# valiant_v1.net
KiCad netlist of a schematic drawn in EAGLE
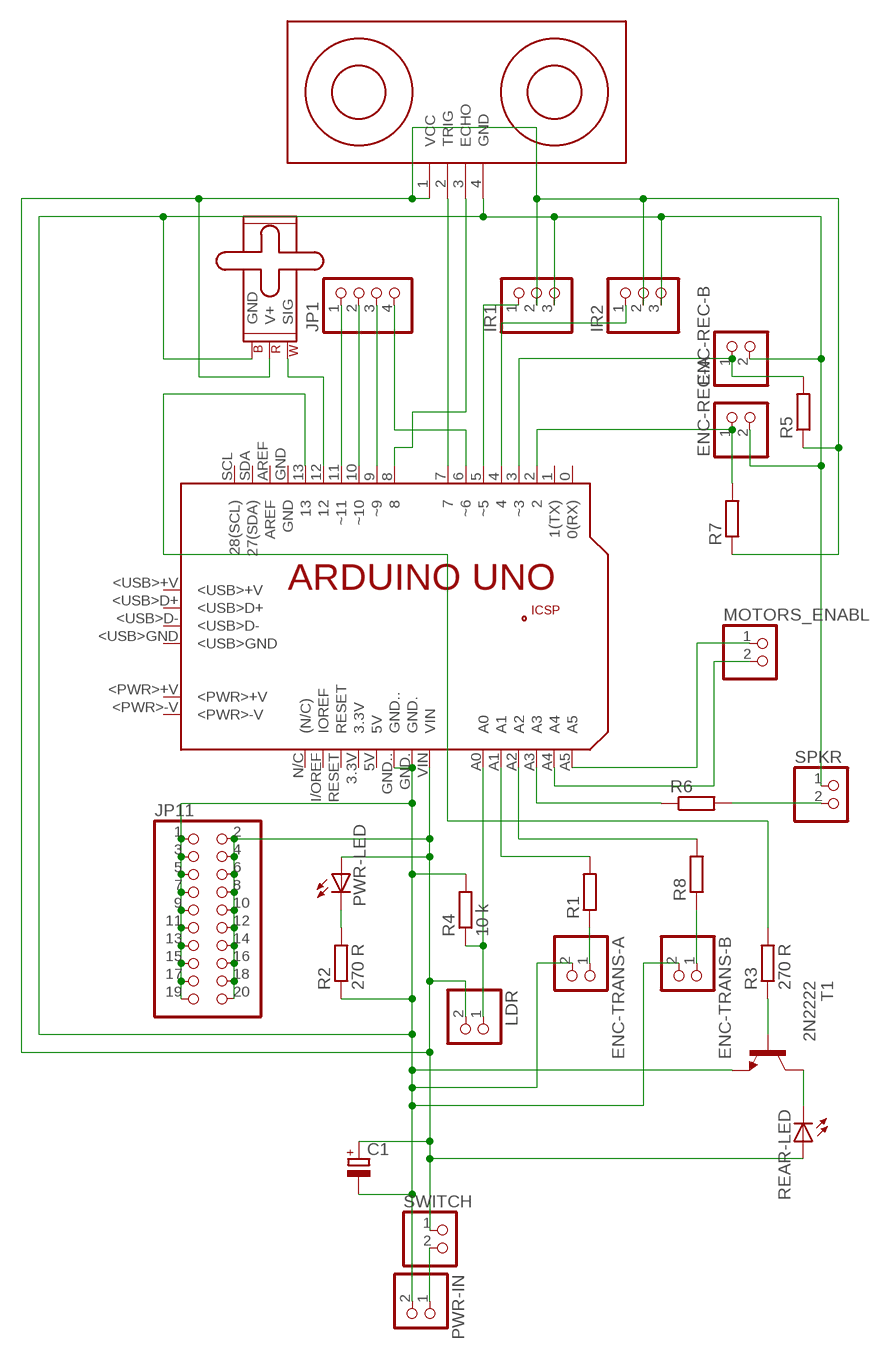
[diagram p0: schematic, sheet 1]

(export (version "E")
  (design (tool "Eeschema 10.0.6"))
  (components
    (comp (ref "C1")
      (value "CPOL-EUE2,5-6E")
      (footprint "eagle-import:E2,5-6E")
      (libsource (lib "eagle-import") (part "CPOL-EUE2,5-6E"))
    )
    (comp (ref "ENC-REC-A")
      (value "PINHD-1X2")
      (footprint "eagle-import:1X02")
      (libsource (lib "eagle-import") (part "PINHD-1X2"))
    )
    (comp (ref "ENC-REC-B")
      (value "PINHD-1X2")
      (footprint "eagle-import:1X02")
      (libsource (lib "eagle-import") (part "PINHD-1X2"))
    )
    (comp (ref "ENC-TRANS-A")
      (value "PINHD-1X2")
      (footprint "eagle-import:1X02")
      (libsource (lib "eagle-import") (part "PINHD-1X2"))
    )
    (comp (ref "ENC-TRANS-B")
      (value "PINHD-1X2")
      (footprint "eagle-import:1X02")
      (libsource (lib "eagle-import") (part "PINHD-1X2"))
    )
    (comp (ref "IR1")
      (value "PINHD-1X3")
      (footprint "eagle-import:1X03")
      (libsource (lib "eagle-import") (part "PINHD-1X3"))
    )
    (comp (ref "IR2")
      (value "PINHD-1X3")
      (footprint "eagle-import:1X03")
      (libsource (lib "eagle-import") (part "PINHD-1X3"))
    )
    (comp (ref "JP1")
      (value "PINHD-1X4")
      (footprint "eagle-import:1X04")
      (libsource (lib "eagle-import") (part "PINHD-1X4"))
    )
    (comp (ref "JP11")
      (value "PINHD-2X10")
      (footprint "eagle-import:2X10")
      (libsource (lib "eagle-import") (part "PINHD-2X10"))
    )
    (comp (ref "LDR")
      (value "PINHD-1X2")
      (footprint "eagle-import:1X02")
      (libsource (lib "eagle-import") (part "PINHD-1X2"))
    )
    (comp (ref "M1")
      (value "SMALL_SERVO")
      (footprint "eagle-import:1X03")
      (libsource (lib "eagle-import") (part "SMALL_SERVO"))
    )
    (comp (ref "MOTORS_ENABLE")
      (value "PINHD-1X2")
      (footprint "eagle-import:1X02")
      (libsource (lib "eagle-import") (part "PINHD-1X2"))
    )
    (comp (ref "PCB1")
      (value "ARDUINO_UNO")
      (footprint "eagle-import:ARDUINO_UNO")
      (libsource (lib "eagle-import") (part "ARDUINO_UNO"))
    )
    (comp (ref "PWR-IN")
      (value "PINHD-1X2")
      (footprint "eagle-import:1X02")
      (libsource (lib "eagle-import") (part "PINHD-1X2"))
    )
    (comp (ref "PWR-LED")
      (value "LED5MM")
      (footprint "eagle-import:LED5MM")
      (libsource (lib "eagle-import") (part "LED5MM"))
    )
    (comp (ref "R1")
      (value "R-EU_0204/7")
      (footprint "eagle-import:0204_7")
      (libsource (lib "eagle-import") (part "R-EU_0204/7"))
    )
    (comp (ref "R2")
      (value "270 R")
      (footprint "eagle-import:0204_7")
      (libsource (lib "eagle-import") (part "R-EU_0204/7"))
    )
    (comp (ref "R3")
      (value "270 R")
      (footprint "eagle-import:0204_7")
      (libsource (lib "eagle-import") (part "R-EU_0204/7"))
    )
    (comp (ref "R4")
      (value "10 k")
      (footprint "eagle-import:0204_7")
      (libsource (lib "eagle-import") (part "R-EU_0204/7"))
    )
    (comp (ref "R5")
      (value "R-EU_0204/7")
      (footprint "eagle-import:0204_7")
      (libsource (lib "eagle-import") (part "R-EU_0204/7"))
    )
    (comp (ref "R6")
      (value "R-EU_0204/7")
      (footprint "eagle-import:0204_7")
      (libsource (lib "eagle-import") (part "R-EU_0204/7"))
    )
    (comp (ref "R7")
      (value "R-EU_0204/7")
      (footprint "eagle-import:0204_7")
      (libsource (lib "eagle-import") (part "R-EU_0204/7"))
    )
    (comp (ref "R8")
      (value "R-EU_0204/7")
      (footprint "eagle-import:0204_7")
      (libsource (lib "eagle-import") (part "R-EU_0204/7"))
    )
    (comp (ref "REAR-LED")
      (value "LED5MM")
      (footprint "eagle-import:LED5MM")
      (libsource (lib "eagle-import") (part "LED5MM"))
    )
    (comp (ref "SPKR")
      (value "PINHD-1X2")
      (footprint "eagle-import:1X02")
      (libsource (lib "eagle-import") (part "PINHD-1X2"))
    )
    (comp (ref "SWITCH")
      (value "PINHD-1X2")
      (footprint "eagle-import:1X02")
      (libsource (lib "eagle-import") (part "PINHD-1X2"))
    )
    (comp (ref "T1")
      (value "2N2222")
      (footprint "eagle-import:TO92-EBC-OVAL")
      (libsource (lib "eagle-import") (part "2N2222"))
    )
    (comp (ref "U$1")
      (value "ULTRASONIC-HC-SR04#V")
      (footprint "eagle-import:ULTRASONIC-HC-SR04#V")
      (libsource (lib "eagle-import") (part "ULTRASONIC-HC-SR04#V"))
    )
  )
  (nets
    (net (code "1") (name "Net-(ENC-REC-A-Pad1)") (class "Default")
      (node (ref "ENC-REC-A") (pin "1") (pinfunction "1_1") (pintype "passive"))
      (node (ref "PCB1") (pin "2") (pinfunction "2_2") (pintype "bidirectional"))
      (node (ref "R7") (pin "2") (pinfunction "2_2") (pintype "passive"))
    )
    (net (code "2") (name "Net-(ENC-TRANS-A-Pad1)") (class "Default")
      (node (ref "ENC-TRANS-A") (pin "1") (pinfunction "1_1") (pintype "passive"))
      (node (ref "R1") (pin "1") (pinfunction "1_1") (pintype "passive"))
    )
    (net (code "3") (name "Net-(ENC-TRANS-B-Pad1)") (class "Default")
      (node (ref "ENC-TRANS-B") (pin "1") (pinfunction "1_1") (pintype "passive"))
      (node (ref "R8") (pin "1") (pinfunction "1_1") (pintype "passive"))
    )
    (net (code "4") (name "Net-(IR2-Pad1)") (class "Default")
      (node (ref "IR2") (pin "1") (pinfunction "1_1") (pintype "passive"))
      (node (ref "PCB1") (pin "4") (pinfunction "4_4") (pintype "bidirectional"))
    )
    (net (code "5") (name "Net-(LDR-Pad1)") (class "Default")
      (node (ref "LDR") (pin "1") (pinfunction "1_1") (pintype "passive"))
      (node (ref "PCB1") (pin "A0") (pinfunction "A0_A0") (pintype "bidirectional"))
      (node (ref "R4") (pin "1") (pinfunction "1_1") (pintype "passive"))
    )
    (net (code "6") (name "Net-(M1-GND)") (class "Default")
      (node (ref "C1") (pin "-") (pinfunction "-_-") (pintype "passive"))
      (node (ref "ENC-REC-A") (pin "2") (pinfunction "2_2") (pintype "passive"))
      (node (ref "ENC-REC-B") (pin "2") (pinfunction "2_2") (pintype "passive"))
      (node (ref "ENC-TRANS-A") (pin "2") (pinfunction "2_2") (pintype "passive"))
      (node (ref "ENC-TRANS-B") (pin "2") (pinfunction "2_2") (pintype "passive"))
      (node (ref "IR1") (pin "3") (pinfunction "3_3") (pintype "passive"))
      (node (ref "IR2") (pin "3") (pinfunction "3_3") (pintype "passive"))
      (node (ref "JP11") (pin "1") (pinfunction "1_1") (pintype "passive"))
      (node (ref "JP11") (pin "11") (pinfunction "11_11") (pintype "passive"))
      (node (ref "JP11") (pin "13") (pinfunction "13_13") (pintype "passive"))
      (node (ref "JP11") (pin "15") (pinfunction "15_15") (pintype "passive"))
      (node (ref "JP11") (pin "17") (pinfunction "17_17") (pintype "passive"))
      (node (ref "JP11") (pin "19") (pinfunction "19_19") (pintype "passive"))
      (node (ref "JP11") (pin "3") (pinfunction "3_3") (pintype "passive"))
      (node (ref "JP11") (pin "5") (pinfunction "5_5") (pintype "passive"))
      (node (ref "JP11") (pin "7") (pinfunction "7_7") (pintype "passive"))
      (node (ref "JP11") (pin "9") (pinfunction "9_9") (pintype "passive"))
      (node (ref "M1") (pin "3") (pinfunction "GND_3") (pintype "bidirectional"))
      (node (ref "PCB1") (pin "GND.") (pinfunction "GND._GND.") (pintype "bidirectional"))
      (node (ref "PCB1") (pin "GND..") (pinfunction "GND.._GND..") (pintype "bidirectional"))
      (node (ref "PWR-IN") (pin "2") (pinfunction "2_2") (pintype "passive"))
      (node (ref "R2") (pin "1") (pinfunction "1_1") (pintype "passive"))
      (node (ref "R4") (pin "2") (pinfunction "2_2") (pintype "passive"))
      (node (ref "SPKR") (pin "1") (pinfunction "1_1") (pintype "passive"))
      (node (ref "T1") (pin "E") (pinfunction "E_E") (pintype "passive"))
      (node (ref "U$1") (pin "4") (pinfunction "GND_4") (pintype "power_in"))
    )
    (net (code "7") (name "Net-(M1-SIG)") (class "Default")
      (node (ref "M1") (pin "1") (pinfunction "SIG_1") (pintype "bidirectional"))
      (node (ref "PCB1") (pin "12") (pinfunction "12_12") (pintype "bidirectional"))
    )
    (net (code "8") (name "Net-(M1-V+)") (class "Default")
      (node (ref "C1") (pin "+") (pinfunction "+_+") (pintype "passive"))
      (node (ref "IR1") (pin "2") (pinfunction "2_2") (pintype "passive"))
      (node (ref "IR2") (pin "2") (pinfunction "2_2") (pintype "passive"))
      (node (ref "JP11") (pin "10") (pinfunction "10_10") (pintype "passive"))
      (node (ref "JP11") (pin "12") (pinfunction "12_12") (pintype "passive"))
      (node (ref "JP11") (pin "14") (pinfunction "14_14") (pintype "passive"))
      (node (ref "JP11") (pin "16") (pinfunction "16_16") (pintype "passive"))
      (node (ref "JP11") (pin "18") (pinfunction "18_18") (pintype "passive"))
      (node (ref "JP11") (pin "2") (pinfunction "2_2") (pintype "passive"))
      (node (ref "JP11") (pin "20") (pinfunction "20_20") (pintype "passive"))
      (node (ref "JP11") (pin "4") (pinfunction "4_4") (pintype "passive"))
      (node (ref "JP11") (pin "6") (pinfunction "6_6") (pintype "passive"))
      (node (ref "JP11") (pin "8") (pinfunction "8_8") (pintype "passive"))
      (node (ref "LDR") (pin "2") (pinfunction "2_2") (pintype "passive"))
      (node (ref "M1") (pin "2") (pinfunction "V+_2") (pintype "bidirectional"))
      (node (ref "PCB1") (pin "VIN") (pinfunction "VIN_VIN") (pintype "bidirectional"))
      (node (ref "PWR-LED") (pin "A") (pinfunction "A_A") (pintype "passive"))
      (node (ref "R5") (pin "1") (pinfunction "1_1") (pintype "passive"))
      (node (ref "R7") (pin "1") (pinfunction "1_1") (pintype "passive"))
      (node (ref "REAR-LED") (pin "A") (pinfunction "A_A") (pintype "passive"))
      (node (ref "SWITCH") (pin "1") (pinfunction "1_1") (pintype "passive"))
      (node (ref "U$1") (pin "1") (pinfunction "VCC_1") (pintype "power_in"))
    )
    (net (code "9") (name "Net-(MOTORS_ENABLE-Pad1)") (class "Default")
      (node (ref "MOTORS_ENABLE") (pin "1") (pinfunction "1_1") (pintype "passive"))
      (node (ref "PCB1") (pin "A5") (pinfunction "A5_A5") (pintype "bidirectional"))
    )
    (net (code "10") (name "Net-(MOTORS_ENABLE-Pad2)") (class "Default")
      (node (ref "MOTORS_ENABLE") (pin "2") (pinfunction "2_2") (pintype "passive"))
      (node (ref "PCB1") (pin "A4") (pinfunction "A4_A4") (pintype "bidirectional"))
    )
    (net (code "11") (name "Net-(PCB1-Pad13)") (class "Default")
      (node (ref "PCB1") (pin "13") (pinfunction "13_13") (pintype "bidirectional"))
      (node (ref "R3") (pin "2") (pinfunction "2_2") (pintype "passive"))
    )
    (net (code "12") (name "Net-(PCB1-PadA1)") (class "Default")
      (node (ref "PCB1") (pin "A1") (pinfunction "A1_A1") (pintype "bidirectional"))
      (node (ref "R1") (pin "2") (pinfunction "2_2") (pintype "passive"))
    )
    (net (code "13") (name "Net-(PCB1-PadA2)") (class "Default")
      (node (ref "PCB1") (pin "A2") (pinfunction "A2_A2") (pintype "bidirectional"))
      (node (ref "R8") (pin "2") (pinfunction "2_2") (pintype "passive"))
    )
    (net (code "14") (name "Net-(PCB1-PadA3)") (class "Default")
      (node (ref "PCB1") (pin "A3") (pinfunction "A3_A3") (pintype "bidirectional"))
      (node (ref "R6") (pin "1") (pinfunction "1_1") (pintype "passive"))
    )
    (net (code "15") (name "Net-(PCB1-~{3})") (class "Default")
      (node (ref "ENC-REC-B") (pin "1") (pinfunction "1_1") (pintype "passive"))
      (node (ref "PCB1") (pin "3") (pinfunction "~{3}_3") (pintype "bidirectional"))
      (node (ref "R5") (pin "2") (pinfunction "2_2") (pintype "passive"))
    )
    (net (code "16") (name "Net-(PCB1-~{5})") (class "Default")
      (node (ref "IR1") (pin "1") (pinfunction "1_1") (pintype "passive"))
      (node (ref "PCB1") (pin "5") (pinfunction "~{5}_5") (pintype "bidirectional"))
    )
    (net (code "17") (name "Net-(PCB1-~{6})") (class "Default")
      (node (ref "JP1") (pin "4") (pinfunction "4_4") (pintype "passive"))
      (node (ref "PCB1") (pin "6") (pinfunction "~{6}_6") (pintype "bidirectional"))
    )
    (net (code "18") (name "Net-(PCB1-~{9})") (class "Default")
      (node (ref "JP1") (pin "3") (pinfunction "3_3") (pintype "passive"))
      (node (ref "PCB1") (pin "9") (pinfunction "~{9}_9") (pintype "bidirectional"))
    )
    (net (code "19") (name "Net-(PCB1-~{10})") (class "Default")
      (node (ref "JP1") (pin "2") (pinfunction "2_2") (pintype "passive"))
      (node (ref "PCB1") (pin "10") (pinfunction "~{10}_10") (pintype "bidirectional"))
    )
    (net (code "20") (name "Net-(PCB1-~{11})") (class "Default")
      (node (ref "JP1") (pin "1") (pinfunction "1_1") (pintype "passive"))
      (node (ref "PCB1") (pin "11") (pinfunction "~{11}_11") (pintype "bidirectional"))
    )
    (net (code "21") (name "Net-(PWR-IN-Pad1)") (class "Default")
      (node (ref "PWR-IN") (pin "1") (pinfunction "1_1") (pintype "passive"))
      (node (ref "SWITCH") (pin "2") (pinfunction "2_2") (pintype "passive"))
    )
    (net (code "22") (name "Net-(PWR-LED-C)") (class "Default")
      (node (ref "PWR-LED") (pin "K") (pinfunction "C_K") (pintype "passive"))
      (node (ref "R2") (pin "2") (pinfunction "2_2") (pintype "passive"))
    )
    (net (code "23") (name "Net-(R3-Pad1)") (class "Default")
      (node (ref "R3") (pin "1") (pinfunction "1_1") (pintype "passive"))
      (node (ref "T1") (pin "B") (pinfunction "B_B") (pintype "passive"))
    )
    (net (code "24") (name "Net-(R6-Pad2)") (class "Default")
      (node (ref "R6") (pin "2") (pinfunction "2_2") (pintype "passive"))
      (node (ref "SPKR") (pin "2") (pinfunction "2_2") (pintype "passive"))
    )
    (net (code "25") (name "Net-(REAR-LED-C)") (class "Default")
      (node (ref "REAR-LED") (pin "K") (pinfunction "C_K") (pintype "passive"))
      (node (ref "T1") (pin "C") (pinfunction "C_C") (pintype "passive"))
    )
    (net (code "26") (name "Net-(U$1-ECHO)") (class "Default")
      (node (ref "PCB1") (pin "8") (pinfunction "8_8") (pintype "bidirectional"))
      (node (ref "U$1") (pin "3") (pinfunction "ECHO_3") (pintype "output"))
    )
    (net (code "27") (name "Net-(U$1-TRIG)") (class "Default")
      (node (ref "PCB1") (pin "7") (pinfunction "7_7") (pintype "bidirectional"))
      (node (ref "U$1") (pin "2") (pinfunction "TRIG_2") (pintype "input"))
    )
    (net (code "28") (name "unconnected-(PCB1-(N{slash}C)-PadN{slash}C)") (class "Default")
      (node (ref "PCB1") (pin "N/C") (pinfunction "(N/C)_N/C") (pintype "bidirectional"))
    )
    (net (code "29") (name "unconnected-(PCB1-0(RX)-Pad0)") (class "Default")
      (node (ref "PCB1") (pin "0") (pinfunction "0(RX)_0") (pintype "bidirectional"))
    )
    (net (code "30") (name "unconnected-(PCB1-1(TX)-Pad1)") (class "Default")
      (node (ref "PCB1") (pin "1") (pinfunction "1(TX)_1") (pintype "bidirectional"))
    )
    (net (code "31") (name "unconnected-(PCB1-27(SDA)-PadSDA)") (class "Default")
      (node (ref "PCB1") (pin "SDA") (pinfunction "27(SDA)_SDA") (pintype "bidirectional"))
    )
    (net (code "32") (name "unconnected-(PCB1-28(SCL)-PadSCL)") (class "Default")
      (node (ref "PCB1") (pin "SCL") (pinfunction "28(SCL)_SCL") (pintype "bidirectional"))
    )
    (net (code "33") (name "unconnected-(PCB1-IOREF-PadI{slash}OREF)") (class "Default")
      (node (ref "PCB1") (pin "I/OREF") (pinfunction "IOREF_I/OREF") (pintype "bidirectional"))
    )
    (net (code "34") (name "unconnected-(PCB1-Pad+5V)") (class "Default")
      (node (ref "PCB1") (pin "+5V") (pinfunction "+5V_+5V") (pintype "bidirectional"))
    )
    (net (code "35") (name "unconnected-(PCB1-Pad3.3V)") (class "Default")
      (node (ref "PCB1") (pin "3.3V") (pinfunction "3.3V_3.3V") (pintype "bidirectional"))
    )
    (net (code "36") (name "unconnected-(PCB1-Pad5V)") (class "Default")
      (node (ref "PCB1") (pin "5V") (pinfunction "5V_5V") (pintype "bidirectional"))
    )
    (net (code "37") (name "unconnected-(PCB1-Pad<PWR>+V)") (class "Default")
      (node (ref "PCB1") (pin "<PWR>+V") (pinfunction "<PWR>+V_<PWR>+V") (pintype "bidirectional"))
    )
    (net (code "38") (name "unconnected-(PCB1-Pad<PWR>-V)") (class "Default")
      (node (ref "PCB1") (pin "<PWR>-V") (pinfunction "<PWR>-V_<PWR>-V") (pintype "bidirectional"))
    )
    (net (code "39") (name "unconnected-(PCB1-Pad<USB>+V)") (class "Default")
      (node (ref "PCB1") (pin "<USB>+V") (pinfunction "<USB>+V_<USB>+V") (pintype "bidirectional"))
    )
    (net (code "40") (name "unconnected-(PCB1-Pad<USB>D+)") (class "Default")
      (node (ref "PCB1") (pin "<USB>D+") (pinfunction "<USB>D+_<USB>D+") (pintype "bidirectional"))
    )
    (net (code "41") (name "unconnected-(PCB1-Pad<USB>D-)") (class "Default")
      (node (ref "PCB1") (pin "<USB>D-") (pinfunction "<USB>D-_<USB>D-") (pintype "bidirectional"))
    )
    (net (code "42") (name "unconnected-(PCB1-Pad<USB>GND)") (class "Default")
      (node (ref "PCB1") (pin "<USB>GND") (pinfunction "<USB>GND_<USB>GND") (pintype "bidirectional"))
    )
    (net (code "43") (name "unconnected-(PCB1-PadAREF)") (class "Default")
      (node (ref "PCB1") (pin "AREF") (pinfunction "AREF_AREF") (pintype "bidirectional"))
    )
    (net (code "44") (name "unconnected-(PCB1-PadGND)") (class "Default")
      (node (ref "PCB1") (pin "GND") (pinfunction "GND_GND") (pintype "bidirectional"))
    )
    (net (code "45") (name "unconnected-(PCB1-PadGND_)") (class "Default")
      (node (ref "PCB1") (pin "GND_") (pinfunction "GND__GND_") (pintype "bidirectional"))
    )
    (net (code "46") (name "unconnected-(PCB1-PadMISO)") (class "Default")
      (node (ref "PCB1") (pin "MISO") (pinfunction "MISO_MISO") (pintype "bidirectional"))
    )
    (net (code "47") (name "unconnected-(PCB1-PadMOSI)") (class "Default")
      (node (ref "PCB1") (pin "MOSI") (pinfunction "MOSI_MOSI") (pintype "bidirectional"))
    )
    (net (code "48") (name "unconnected-(PCB1-PadRESET)") (class "Default")
      (node (ref "PCB1") (pin "RESET") (pinfunction "RESET_RESET") (pintype "bidirectional"))
    )
    (net (code "49") (name "unconnected-(PCB1-PadRESET.)") (class "Default")
      (node (ref "PCB1") (pin "RESET.") (pinfunction "RESET._RESET.") (pintype "bidirectional"))
    )
    (net (code "50") (name "unconnected-(PCB1-PadSCK)") (class "Default")
      (node (ref "PCB1") (pin "SCK") (pinfunction "SCK_SCK") (pintype "bidirectional"))
    )
  )
)
